# board.net
KiCad netlist of a schematic drawn in EAGLE
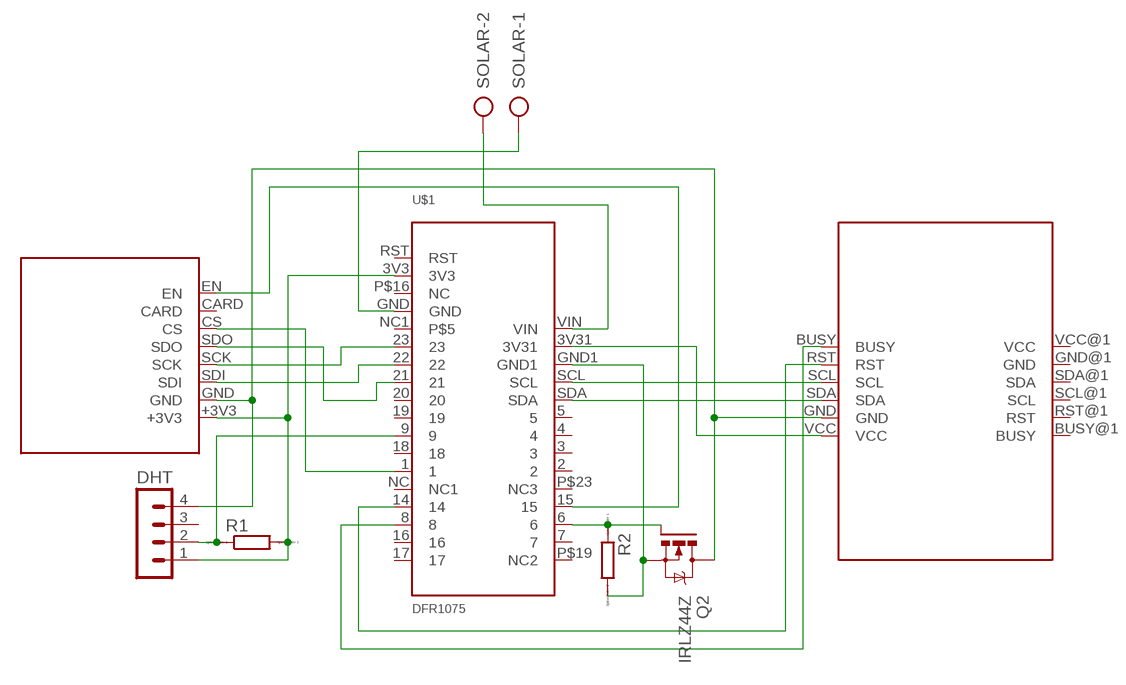
[diagram p0: schematic, sheet 1]

(export (version "E")
  (design (tool "Eeschema 10.0.6"))
  (components
    (comp (ref "DHT")
      (value "MA04-1")
      (footprint "eagle-import:MA04-1")
      (libsource (lib "eagle-import") (part "MA04-1"))
    )
    (comp (ref "Q2")
      (value "IRLZ44Z")
      (footprint "eagle-import:TO220BH")
      (libsource (lib "eagle-import") (part "IRLZ44Z"))
    )
    (comp (ref "R1")
      (value "R0207/10")
      (footprint "eagle-import:0207_10")
      (libsource (lib "eagle-import") (part "R0207/10"))
    )
    (comp (ref "R2")
      (value "R0207/10")
      (footprint "eagle-import:0207_10")
      (libsource (lib "eagle-import") (part "R0207/10"))
    )
    (comp (ref "SOLAR")
      (value "AK300/2")
      (footprint "eagle-import:AK300_2")
      (libsource (lib "eagle-import") (part "AK300/2"))
    )
    (comp (ref "U$1")
      (value "DFR1075")
      (footprint "eagle-import:DFR1075")
      (libsource (lib "eagle-import") (part "DFR1075"))
    )
    (comp (ref "U$2")
      (value "1.9INCH_WAVESHARE_E-PAPER")
      (footprint "eagle-import:1.9INCH_WAVESHARE_E-PAPER")
      (libsource (lib "eagle-import") (part "1.9INCH_WAVESHARE_E-PAPER"))
    )
    (comp (ref "U$3")
      (value "LASKAKIT-MICROSD-READER")
      (footprint "eagle-import:LASKAKIT-MICROSD-READER")
      (libsource (lib "eagle-import") (part "LASKAKIT-MICROSD-READER"))
    )
  )
  (nets
    (net (code "1") (name "Net-(DHT-Pad1)") (class "Default")
      (node (ref "DHT") (pin "1") (pinfunction "1_1") (pintype "passive"))
      (node (ref "R1") (pin "2") (pinfunction "2_2") (pintype "passive"))
      (node (ref "U$1") (pin "3V3") (pinfunction "3V3_3V3") (pintype "bidirectional"))
      (node (ref "U$3") (pin "+3V3") (pinfunction "+3V3_+3V3") (pintype "bidirectional"))
    )
    (net (code "2") (name "Net-(DHT-Pad2)") (class "Default")
      (node (ref "DHT") (pin "2") (pinfunction "2_2") (pintype "passive"))
      (node (ref "R1") (pin "1") (pinfunction "1_1") (pintype "passive"))
      (node (ref "U$1") (pin "9") (pinfunction "9_9") (pintype "bidirectional"))
    )
    (net (code "3") (name "Net-(DHT-Pad4)") (class "Default")
      (node (ref "DHT") (pin "4") (pinfunction "4_4") (pintype "passive"))
      (node (ref "Q2") (pin "D") (pinfunction "D_D") (pintype "passive"))
      (node (ref "U$2") (pin "GND") (pinfunction "GND_GND") (pintype "bidirectional"))
      (node (ref "U$3") (pin "GND") (pinfunction "GND_GND") (pintype "bidirectional"))
    )
    (net (code "4") (name "Net-(Q2-PadG)") (class "Default")
      (node (ref "Q2") (pin "G") (pinfunction "G_G") (pintype "passive"))
      (node (ref "R2") (pin "1") (pinfunction "1_1") (pintype "passive"))
      (node (ref "U$1") (pin "6") (pinfunction "6_6") (pintype "bidirectional"))
    )
    (net (code "5") (name "Net-(Q2-PadS)") (class "Default")
      (node (ref "Q2") (pin "S") (pinfunction "S_S") (pintype "passive"))
      (node (ref "R2") (pin "2") (pinfunction "2_2") (pintype "passive"))
      (node (ref "U$1") (pin "GND1") (pinfunction "GND1_GND1") (pintype "bidirectional"))
    )
    (net (code "6") (name "Net-(SOLARA-KL)") (class "Default")
      (node (ref "SOLAR") (pin "1") (pinfunction "KL_1") (pintype "passive"))
      (node (ref "U$1") (pin "GND") (pinfunction "GND_GND") (pintype "bidirectional"))
    )
    (net (code "7") (name "Net-(SOLARB-KL)") (class "Default")
      (node (ref "SOLAR") (pin "2") (pinfunction "KL_2") (pintype "passive"))
      (node (ref "U$1") (pin "VIN") (pinfunction "VIN_VIN") (pintype "bidirectional"))
    )
    (net (code "8") (name "Net-(U$1-Pad1)") (class "Default")
      (node (ref "U$1") (pin "1") (pinfunction "1_1") (pintype "bidirectional"))
      (node (ref "U$3") (pin "CS") (pinfunction "CS_CS") (pintype "bidirectional"))
    )
    (net (code "9") (name "Net-(U$1-Pad3V31)") (class "Default")
      (node (ref "U$1") (pin "3V31") (pinfunction "3V31_3V31") (pintype "bidirectional"))
      (node (ref "U$2") (pin "VCC") (pinfunction "VCC_VCC") (pintype "bidirectional"))
    )
    (net (code "10") (name "Net-(U$1-Pad8)") (class "Default")
      (node (ref "U$1") (pin "8") (pinfunction "8_8") (pintype "bidirectional"))
      (node (ref "U$2") (pin "BUSY") (pinfunction "BUSY_BUSY") (pintype "bidirectional"))
    )
    (net (code "11") (name "Net-(U$1-Pad14)") (class "Default")
      (node (ref "U$1") (pin "14") (pinfunction "14_14") (pintype "bidirectional"))
      (node (ref "U$2") (pin "RST") (pinfunction "RST_RST") (pintype "bidirectional"))
    )
    (net (code "12") (name "Net-(U$1-Pad15)") (class "Default")
      (node (ref "U$1") (pin "15") (pinfunction "15_15") (pintype "bidirectional"))
      (node (ref "U$3") (pin "EN") (pinfunction "EN_EN") (pintype "bidirectional"))
    )
    (net (code "13") (name "Net-(U$1-Pad21)") (class "Default")
      (node (ref "U$1") (pin "21") (pinfunction "21_21") (pintype "bidirectional"))
      (node (ref "U$3") (pin "SDO") (pinfunction "SDO_SDO") (pintype "bidirectional"))
    )
    (net (code "14") (name "Net-(U$1-Pad22)") (class "Default")
      (node (ref "U$1") (pin "22") (pinfunction "22_22") (pintype "bidirectional"))
      (node (ref "U$3") (pin "SDI") (pinfunction "SDI_SDI") (pintype "bidirectional"))
    )
    (net (code "15") (name "Net-(U$1-Pad23)") (class "Default")
      (node (ref "U$1") (pin "23") (pinfunction "23_23") (pintype "bidirectional"))
      (node (ref "U$3") (pin "SCK") (pinfunction "SCK_SCK") (pintype "bidirectional"))
    )
    (net (code "16") (name "Net-(U$1-PadSCL)") (class "Default")
      (node (ref "U$1") (pin "SCL") (pinfunction "SCL_SCL") (pintype "bidirectional"))
      (node (ref "U$2") (pin "SCL") (pinfunction "SCL_SCL") (pintype "bidirectional"))
    )
    (net (code "17") (name "Net-(U$1-PadSDA)") (class "Default")
      (node (ref "U$1") (pin "SDA") (pinfunction "SDA_SDA") (pintype "bidirectional"))
      (node (ref "U$2") (pin "SDA") (pinfunction "SDA_SDA") (pintype "bidirectional"))
    )
    (net (code "18") (name "unconnected-(DHT-Pad3)") (class "Default")
      (node (ref "DHT") (pin "3") (pinfunction "3_3") (pintype "passive"))
    )
    (net (code "19") (name "unconnected-(U$1-NC-PadP$16)") (class "Default")
      (node (ref "U$1") (pin "P$16") (pinfunction "NC_P$16") (pintype "bidirectional"))
    )
    (net (code "20") (name "unconnected-(U$1-NC1-PadNC)") (class "Default")
      (node (ref "U$1") (pin "NC") (pinfunction "NC1_NC") (pintype "bidirectional"))
    )
    (net (code "21") (name "unconnected-(U$1-NC2-PadP$19)") (class "Default")
      (node (ref "U$1") (pin "P$19") (pinfunction "NC2_P$19") (pintype "bidirectional"))
    )
    (net (code "22") (name "unconnected-(U$1-NC3-PadP$23)") (class "Default")
      (node (ref "U$1") (pin "P$23") (pinfunction "NC3_P$23") (pintype "bidirectional"))
    )
    (net (code "23") (name "unconnected-(U$1-P$5-PadNC1)") (class "Default")
      (node (ref "U$1") (pin "NC1") (pinfunction "P$5_NC1") (pintype "bidirectional"))
    )
    (net (code "24") (name "unconnected-(U$1-Pad2)") (class "Default")
      (node (ref "U$1") (pin "2") (pinfunction "2_2") (pintype "bidirectional"))
    )
    (net (code "25") (name "unconnected-(U$1-Pad3)") (class "Default")
      (node (ref "U$1") (pin "3") (pinfunction "3_3") (pintype "bidirectional"))
    )
    (net (code "26") (name "unconnected-(U$1-Pad4)") (class "Default")
      (node (ref "U$1") (pin "4") (pinfunction "4_4") (pintype "bidirectional"))
    )
    (net (code "27") (name "unconnected-(U$1-Pad5)") (class "Default")
      (node (ref "U$1") (pin "5") (pinfunction "5_5") (pintype "bidirectional"))
    )
    (net (code "28") (name "unconnected-(U$1-Pad7)") (class "Default")
      (node (ref "U$1") (pin "7") (pinfunction "7_7") (pintype "bidirectional"))
    )
    (net (code "29") (name "unconnected-(U$1-Pad16)") (class "Default")
      (node (ref "U$1") (pin "16") (pinfunction "16_16") (pintype "bidirectional"))
    )
    (net (code "30") (name "unconnected-(U$1-Pad17)") (class "Default")
      (node (ref "U$1") (pin "17") (pinfunction "17_17") (pintype "bidirectional"))
    )
    (net (code "31") (name "unconnected-(U$1-Pad18)") (class "Default")
      (node (ref "U$1") (pin "18") (pinfunction "18_18") (pintype "bidirectional"))
    )
    (net (code "32") (name "unconnected-(U$1-Pad19)") (class "Default")
      (node (ref "U$1") (pin "19") (pinfunction "19_19") (pintype "bidirectional"))
    )
    (net (code "33") (name "unconnected-(U$1-Pad20)") (class "Default")
      (node (ref "U$1") (pin "20") (pinfunction "20_20") (pintype "bidirectional"))
    )
    (net (code "34") (name "unconnected-(U$1-PadRST)") (class "Default")
      (node (ref "U$1") (pin "RST") (pinfunction "RST_RST") (pintype "bidirectional"))
    )
    (net (code "35") (name "unconnected-(U$2-BUSY-PadBUSY@1)") (class "Default")
      (node (ref "U$2") (pin "BUSY@1") (pinfunction "BUSY_BUSY@1") (pintype "bidirectional"))
    )
    (net (code "36") (name "unconnected-(U$2-GND-PadGND@1)") (class "Default")
      (node (ref "U$2") (pin "GND@1") (pinfunction "GND_GND@1") (pintype "bidirectional"))
    )
    (net (code "37") (name "unconnected-(U$2-RST-PadRST@1)") (class "Default")
      (node (ref "U$2") (pin "RST@1") (pinfunction "RST_RST@1") (pintype "bidirectional"))
    )
    (net (code "38") (name "unconnected-(U$2-SCL-PadSCL@1)") (class "Default")
      (node (ref "U$2") (pin "SCL@1") (pinfunction "SCL_SCL@1") (pintype "bidirectional"))
    )
    (net (code "39") (name "unconnected-(U$2-SDA-PadSDA@1)") (class "Default")
      (node (ref "U$2") (pin "SDA@1") (pinfunction "SDA_SDA@1") (pintype "bidirectional"))
    )
    (net (code "40") (name "unconnected-(U$2-VCC-PadVCC@1)") (class "Default")
      (node (ref "U$2") (pin "VCC@1") (pinfunction "VCC_VCC@1") (pintype "bidirectional"))
    )
    (net (code "41") (name "unconnected-(U$3-PadCARD)") (class "Default")
      (node (ref "U$3") (pin "CARD") (pinfunction "CARD_CARD") (pintype "bidirectional"))
    )
  )
)
